# 1-Schematic_8052Explorer_DIP.net
KiCad netlist of a schematic drawn in EasyEDA
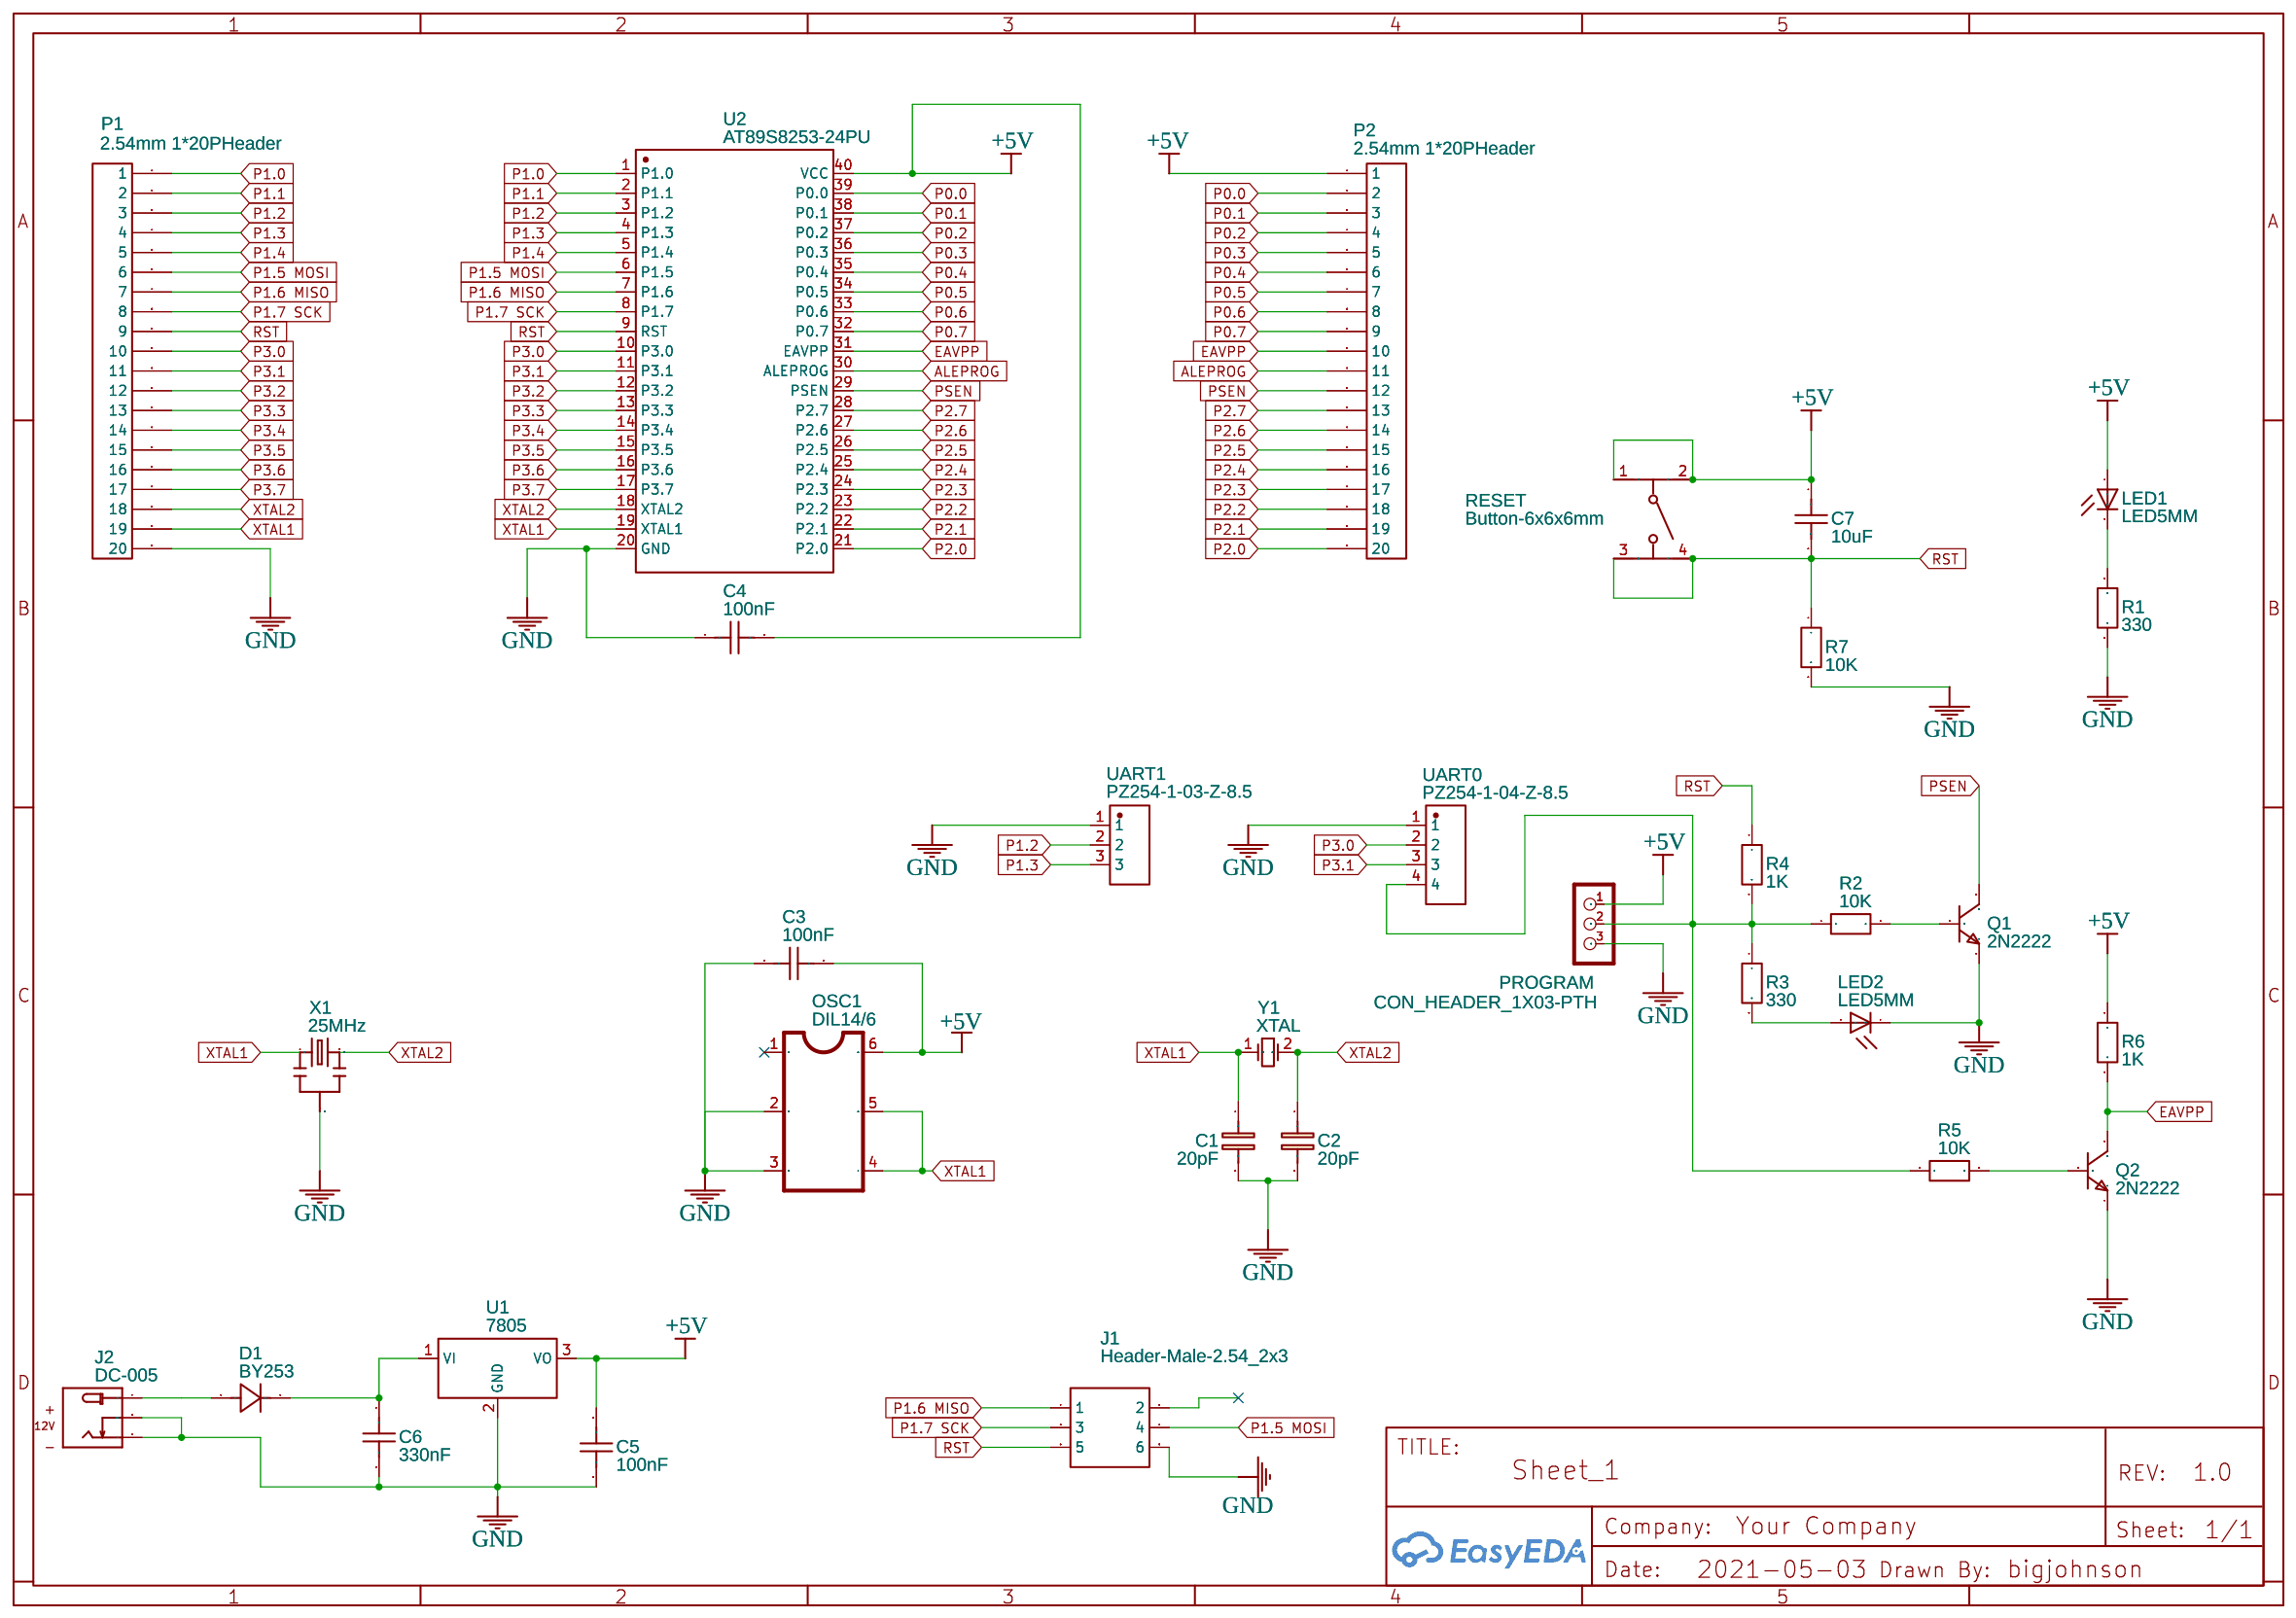
[diagram p0: schematic sheet]

(export (version "E")
  (design (tool "Eeschema 10.0.6"))
  (components
    (comp (ref "C1")
      (value "20pF")
      (fields (field (name "BOM_Supplier Part") "9000274010"))
      (libsource (lib "") (part "20pF copy"))
    )
    (comp (ref "C2")
      (value "20pF")
      (fields (field (name "BOM_Supplier Part") "9000274010"))
      (libsource (lib "") (part "20pF copy"))
    )
    (comp (ref "C3")
      (value "100nF")
      (fields
        (field (name "BOM_Manufacturer Part") "CT4-0805B103 K500")
        (field (name "BOM_Supplier Part") "C8033")
      )
      (libsource (lib "") (part "CT4-0805B103 K500"))
    )
    (comp (ref "C4")
      (value "100nF")
      (fields
        (field (name "BOM_Manufacturer Part") "CT4-0805B103 K500")
        (field (name "BOM_Supplier Part") "C8033")
      )
      (libsource (lib "") (part "CT4-0805B103 K500"))
    )
    (comp (ref "C5")
      (value "100nF")
      (fields
        (field (name "BOM_Manufacturer Part") "CT4-0805B103 K500")
        (field (name "BOM_Supplier Part") "C8033")
      )
      (libsource (lib "") (part "CT4-0805B103 K500_1"))
    )
    (comp (ref "C6")
      (value "330nF")
      (fields
        (field (name "BOM_Manufacturer Part") "CT4-0805B103 K500")
        (field (name "BOM_Supplier Part") "C8033")
      )
      (libsource (lib "") (part "CT4-0805B103 K500_1"))
    )
    (comp (ref "C7")
      (value "10uF")
      (fields
        (field (name "BOM_Manufacturer Part") "CT4-0805B103 K500")
        (field (name "BOM_Supplier Part") "C8033")
      )
      (libsource (lib "") (part "CT4-0805B103 K500_1"))
    )
    (comp (ref "D1")
      (value "BY253")
      (fields (field (name "BOM_Manufacturer Part") "MUR460") (field (name "BOM_Supplier Part") "C2990844"))
      (libsource (lib "") (part "MUR460_C2990844"))
    )
    (comp (ref "J1")
      (value "Header-Male-2.54_2x3")
      (fields (field (name "BOM_Supplier Part") "C65114"))
      (libsource (lib "") (part "Header-Male-2.54_2x3"))
    )
    (comp (ref "J2") (value "DC-005") (libsource (lib "") (part "DC-005")))
    (comp (ref "LED1") (value "LED5MM") (libsource (lib "") (part "LED5MM")))
    (comp (ref "LED2") (value "LED5MM") (libsource (lib "") (part "LED5MM_1")))
    (comp (ref "OSC1") (value "DIL14/6") (libsource (lib "") (part "DIL14/3")))
    (comp (ref "P1")
      (value "2.54mm 1*20PHeader")
      (fields (field (name "BOM_Supplier Part") "C50981"))
      (libsource (lib "") (part "2.54mm 1*20PHeader"))
    )
    (comp (ref "P2")
      (value "2.54mm 1*20PHeader")
      (fields (field (name "BOM_Supplier Part") "C50981"))
      (libsource (lib "") (part "2.54mm 1*20PHeader_1"))
    )
    (comp (ref "PROGRAM") (value "CON_HEADER_1X03-PTH") (libsource (lib "") (part "CON_HEADER_1X03-PTH")))
    (comp (ref "Q1")
      (value "2N2222")
      (fields (field (name "BOM_Supplier Part") "C118536"))
      (libsource (lib "") (part "2N2222"))
    )
    (comp (ref "Q2")
      (value "2N2222")
      (fields (field (name "BOM_Supplier Part") "C118536"))
      (libsource (lib "") (part "2N2222"))
    )
    (comp (ref "R1") (value "330") (libsource (lib "") (part "Res_AXIAL-0.4(1/4W)_EU")))
    (comp (ref "R2") (value "10K") (libsource (lib "") (part "Res_AXIAL-0.4(1/4W)_EU_1")))
    (comp (ref "R3") (value "330") (libsource (lib "") (part "Res_AXIAL-0.4(1/4W)_EU")))
    (comp (ref "R4") (value "1K") (libsource (lib "") (part "Res_AXIAL-0.4(1/4W)_EU")))
    (comp (ref "R5") (value "10K") (libsource (lib "") (part "Res_AXIAL-0.4(1/4W)_EU_1")))
    (comp (ref "R6") (value "1K") (libsource (lib "") (part "Res_AXIAL-0.4(1/4W)_EU")))
    (comp (ref "R7") (value "10K") (libsource (lib "") (part "Res_AXIAL-0.4(1/4W)_EU")))
    (comp (ref "RESET")
      (value "Button-6x6x6mm")
      (fields
        (field (name "BOM_Manufacturer Part") "Switch,6*6*6Plastic head,260G, 0.25mm,Straight line")
        (field (name "BOM_Supplier Part") "C71836")
      )
      (libsource (lib "") (part "Button-6x6x6mm"))
    )
    (comp (ref "U1")
      (value "7805")
      (fields (field (name "BOM_Supplier Part") "C305416"))
      (libsource (lib "") (part "7805"))
    )
    (comp (ref "U2") (value "AT89S8253-24PU") (libsource (lib "") (part "AT89S8253-24PU")))
    (comp (ref "UART0")
      (value "PZ254-1-04-Z-8.5")
      (fields (field (name "BOM_Supplier Part") "C2894927"))
      (libsource (lib "") (part "PZ254-1-04-Z-8.5"))
    )
    (comp (ref "UART1")
      (value "PZ254-1-03-Z-8.5")
      (fields (field (name "BOM_Supplier Part") "C2894926"))
      (libsource (lib "") (part "PZ254-1-03-Z-8.5"))
    )
    (comp (ref "X1")
      (value "25MHz")
      (fields
        (field (name "BOM_Manufacturer Part") "Resonator 433.92MHZ")
        (field (name "BOM_Supplier Part") "C71016")
      )
      (libsource (lib "") (part "Ceramic Resonator 16 MHz"))
    )
    (comp (ref "Y1") (value "XTAL") (libsource (lib "") (part "XTAL")))
  )
  (nets
    (net (code "1") (name "+5V") (class "Default")
      (node (ref "C3") (pin "2") (pinfunction "2_2") (pintype "unspecified"))
      (node (ref "C4") (pin "2") (pinfunction "2_2") (pintype "unspecified"))
      (node (ref "C5") (pin "1") (pinfunction "1_1") (pintype "unspecified"))
      (node (ref "C7") (pin "1") (pinfunction "1_1") (pintype "unspecified"))
      (node (ref "LED1") (pin "A") (pinfunction "A_A") (pintype "unspecified"))
      (node (ref "OSC1") (pin "6") (pinfunction "6_6") (pintype "unspecified"))
      (node (ref "P2") (pin "1") (pinfunction "1_1") (pintype "input"))
      (node (ref "PROGRAM") (pin "1") (pinfunction "1_1") (pintype "unspecified"))
      (node (ref "R6") (pin "1") (pinfunction "1_1") (pintype "unspecified"))
      (node (ref "RESET") (pin "1") (pinfunction "1_1") (pintype "unspecified"))
      (node (ref "RESET") (pin "2") (pinfunction "2_2") (pintype "unspecified"))
      (node (ref "U1") (pin "3") (pinfunction "VO_3") (pintype "unspecified"))
      (node (ref "U2") (pin "40") (pinfunction "VCC_40") (pintype "unspecified"))
    )
    (net (code "2") (name "ALEPROG") (class "Default")
      (node (ref "P2") (pin "11") (pinfunction "11_11") (pintype "input"))
      (node (ref "U2") (pin "30") (pinfunction "ALEPROG_30") (pintype "unspecified"))
    )
    (net (code "3") (name "EAVPP") (class "Default")
      (node (ref "P2") (pin "10") (pinfunction "10_10") (pintype "input"))
      (node (ref "Q2") (pin "3") (pinfunction "C_3") (pintype "unspecified"))
      (node (ref "R6") (pin "2") (pinfunction "2_2") (pintype "unspecified"))
      (node (ref "U2") (pin "31") (pinfunction "EAVPP_31") (pintype "unspecified"))
    )
    (net (code "4") (name "GND") (class "Default")
      (node (ref "C1") (pin "2") (pinfunction "1_2") (pintype "unspecified"))
      (node (ref "C2") (pin "2") (pinfunction "1_2") (pintype "unspecified"))
      (node (ref "C3") (pin "1") (pinfunction "1_1") (pintype "unspecified"))
      (node (ref "C4") (pin "1") (pinfunction "1_1") (pintype "unspecified"))
      (node (ref "C5") (pin "2") (pinfunction "2_2") (pintype "unspecified"))
      (node (ref "C6") (pin "2") (pinfunction "2_2") (pintype "unspecified"))
      (node (ref "J1") (pin "6") (pinfunction "6_6") (pintype "input"))
      (node (ref "J2") (pin "-1") (pinfunction "-_-1") (pintype "unspecified"))
      (node (ref "J2") (pin "-2") (pinfunction "CDN_-2") (pintype "unspecified"))
      (node (ref "LED2") (pin "K") (pinfunction "C_K") (pintype "unspecified"))
      (node (ref "OSC1") (pin "2") (pinfunction "2_2") (pintype "unspecified"))
      (node (ref "OSC1") (pin "3") (pinfunction "3_3") (pintype "unspecified"))
      (node (ref "P1") (pin "20") (pinfunction "20_20") (pintype "input"))
      (node (ref "PROGRAM") (pin "3") (pinfunction "3_3") (pintype "unspecified"))
      (node (ref "Q1") (pin "1") (pinfunction "E_1") (pintype "unspecified"))
      (node (ref "Q2") (pin "1") (pinfunction "E_1") (pintype "unspecified"))
      (node (ref "R1") (pin "2") (pinfunction "2_2") (pintype "unspecified"))
      (node (ref "R7") (pin "2") (pinfunction "2_2") (pintype "unspecified"))
      (node (ref "U1") (pin "2") (pinfunction "GND_2") (pintype "unspecified"))
      (node (ref "U2") (pin "20") (pinfunction "GND_20") (pintype "unspecified"))
      (node (ref "UART0") (pin "1") (pinfunction "1_1") (pintype "unspecified"))
      (node (ref "UART1") (pin "1") (pinfunction "1_1") (pintype "unspecified"))
      (node (ref "X1") (pin "2") (pinfunction "2_2") (pintype "unspecified"))
    )
    (net (code "5") (name "Net-(D1-A)") (class "Default")
      (node (ref "D1") (pin "2") (pinfunction "A_2") (pintype "unspecified"))
      (node (ref "J2") (pin "+") (pinfunction "+_+") (pintype "unspecified"))
    )
    (net (code "6") (name "Net-(D1-K)") (class "Default")
      (node (ref "C6") (pin "1") (pinfunction "1_1") (pintype "unspecified"))
      (node (ref "D1") (pin "1") (pinfunction "K_1") (pintype "unspecified"))
      (node (ref "U1") (pin "1") (pinfunction "VI_1") (pintype "unspecified"))
    )
    (net (code "7") (name "Net-(LED1-C)") (class "Default")
      (node (ref "LED1") (pin "K") (pinfunction "C_K") (pintype "unspecified"))
      (node (ref "R1") (pin "1") (pinfunction "1_1") (pintype "unspecified"))
    )
    (net (code "8") (name "Net-(LED2-PadA)") (class "Default")
      (node (ref "LED2") (pin "A") (pinfunction "A_A") (pintype "unspecified"))
      (node (ref "R3") (pin "2") (pinfunction "2_2") (pintype "unspecified"))
    )
    (net (code "9") (name "Net-(PROGRAM-Pad2)") (class "Default")
      (node (ref "PROGRAM") (pin "2") (pinfunction "2_2") (pintype "unspecified"))
      (node (ref "R2") (pin "1") (pinfunction "1_1") (pintype "unspecified"))
      (node (ref "R3") (pin "1") (pinfunction "1_1") (pintype "unspecified"))
      (node (ref "R4") (pin "2") (pinfunction "2_2") (pintype "unspecified"))
      (node (ref "R5") (pin "1") (pinfunction "1_1") (pintype "unspecified"))
      (node (ref "UART0") (pin "4") (pinfunction "4_4") (pintype "unspecified"))
    )
    (net (code "10") (name "Net-(Q1-B)") (class "Default")
      (node (ref "Q1") (pin "2") (pinfunction "B_2") (pintype "unspecified"))
      (node (ref "R2") (pin "2") (pinfunction "2_2") (pintype "unspecified"))
    )
    (net (code "11") (name "Net-(Q2-B)") (class "Default")
      (node (ref "Q2") (pin "2") (pinfunction "B_2") (pintype "unspecified"))
      (node (ref "R5") (pin "2") (pinfunction "2_2") (pintype "unspecified"))
    )
    (net (code "12") (name "P0.0") (class "Default")
      (node (ref "P2") (pin "2") (pinfunction "2_2") (pintype "input"))
      (node (ref "U2") (pin "39") (pinfunction "P0.0_39") (pintype "unspecified"))
    )
    (net (code "13") (name "P0.1") (class "Default")
      (node (ref "P2") (pin "3") (pinfunction "3_3") (pintype "input"))
      (node (ref "U2") (pin "38") (pinfunction "P0.1_38") (pintype "unspecified"))
    )
    (net (code "14") (name "P0.2") (class "Default")
      (node (ref "P2") (pin "4") (pinfunction "4_4") (pintype "input"))
      (node (ref "U2") (pin "37") (pinfunction "P0.2_37") (pintype "unspecified"))
    )
    (net (code "15") (name "P0.3") (class "Default")
      (node (ref "P2") (pin "5") (pinfunction "5_5") (pintype "input"))
      (node (ref "U2") (pin "36") (pinfunction "P0.3_36") (pintype "unspecified"))
    )
    (net (code "16") (name "P0.4") (class "Default")
      (node (ref "P2") (pin "6") (pinfunction "6_6") (pintype "input"))
      (node (ref "U2") (pin "35") (pinfunction "P0.4_35") (pintype "unspecified"))
    )
    (net (code "17") (name "P0.5") (class "Default")
      (node (ref "P2") (pin "7") (pinfunction "7_7") (pintype "input"))
      (node (ref "U2") (pin "34") (pinfunction "P0.5_34") (pintype "unspecified"))
    )
    (net (code "18") (name "P0.6") (class "Default")
      (node (ref "P2") (pin "8") (pinfunction "8_8") (pintype "input"))
      (node (ref "U2") (pin "33") (pinfunction "P0.6_33") (pintype "unspecified"))
    )
    (net (code "19") (name "P0.7") (class "Default")
      (node (ref "P2") (pin "9") (pinfunction "9_9") (pintype "input"))
      (node (ref "U2") (pin "32") (pinfunction "P0.7_32") (pintype "unspecified"))
    )
    (net (code "20") (name "P1.0") (class "Default")
      (node (ref "P1") (pin "1") (pinfunction "1_1") (pintype "input"))
      (node (ref "U2") (pin "1") (pinfunction "P1.0_1") (pintype "unspecified"))
    )
    (net (code "21") (name "P1.1") (class "Default")
      (node (ref "P1") (pin "2") (pinfunction "2_2") (pintype "input"))
      (node (ref "U2") (pin "2") (pinfunction "P1.1_2") (pintype "unspecified"))
    )
    (net (code "22") (name "P1.2") (class "Default")
      (node (ref "P1") (pin "3") (pinfunction "3_3") (pintype "input"))
      (node (ref "U2") (pin "3") (pinfunction "P1.2_3") (pintype "unspecified"))
      (node (ref "UART1") (pin "2") (pinfunction "2_2") (pintype "unspecified"))
    )
    (net (code "23") (name "P1.3") (class "Default")
      (node (ref "P1") (pin "4") (pinfunction "4_4") (pintype "input"))
      (node (ref "U2") (pin "4") (pinfunction "P1.3_4") (pintype "unspecified"))
      (node (ref "UART1") (pin "3") (pinfunction "3_3") (pintype "unspecified"))
    )
    (net (code "24") (name "P1.4") (class "Default")
      (node (ref "P1") (pin "5") (pinfunction "5_5") (pintype "input"))
      (node (ref "U2") (pin "5") (pinfunction "P1.4_5") (pintype "unspecified"))
    )
    (net (code "25") (name "P1.5 MOSI") (class "Default")
      (node (ref "J1") (pin "4") (pinfunction "4_4") (pintype "input"))
      (node (ref "P1") (pin "6") (pinfunction "6_6") (pintype "input"))
      (node (ref "U2") (pin "6") (pinfunction "P1.5_6") (pintype "unspecified"))
    )
    (net (code "26") (name "P1.6 MISO") (class "Default")
      (node (ref "J1") (pin "1") (pinfunction "1_1") (pintype "input"))
      (node (ref "P1") (pin "7") (pinfunction "7_7") (pintype "input"))
      (node (ref "U2") (pin "7") (pinfunction "P1.6_7") (pintype "unspecified"))
    )
    (net (code "27") (name "P1.7 SCK") (class "Default")
      (node (ref "J1") (pin "3") (pinfunction "3_3") (pintype "input"))
      (node (ref "P1") (pin "8") (pinfunction "8_8") (pintype "input"))
      (node (ref "U2") (pin "8") (pinfunction "P1.7_8") (pintype "unspecified"))
    )
    (net (code "28") (name "P2.0") (class "Default")
      (node (ref "P2") (pin "20") (pinfunction "20_20") (pintype "input"))
      (node (ref "U2") (pin "21") (pinfunction "P2.0_21") (pintype "unspecified"))
    )
    (net (code "29") (name "P2.1") (class "Default")
      (node (ref "P2") (pin "19") (pinfunction "19_19") (pintype "input"))
      (node (ref "U2") (pin "22") (pinfunction "P2.1_22") (pintype "unspecified"))
    )
    (net (code "30") (name "P2.2") (class "Default")
      (node (ref "P2") (pin "18") (pinfunction "18_18") (pintype "input"))
      (node (ref "U2") (pin "23") (pinfunction "P2.2_23") (pintype "unspecified"))
    )
    (net (code "31") (name "P2.3") (class "Default")
      (node (ref "P2") (pin "17") (pinfunction "17_17") (pintype "input"))
      (node (ref "U2") (pin "24") (pinfunction "P2.3_24") (pintype "unspecified"))
    )
    (net (code "32") (name "P2.4") (class "Default")
      (node (ref "P2") (pin "16") (pinfunction "16_16") (pintype "input"))
      (node (ref "U2") (pin "25") (pinfunction "P2.4_25") (pintype "unspecified"))
    )
    (net (code "33") (name "P2.5") (class "Default")
      (node (ref "P2") (pin "15") (pinfunction "15_15") (pintype "input"))
      (node (ref "U2") (pin "26") (pinfunction "P2.5_26") (pintype "unspecified"))
    )
    (net (code "34") (name "P2.6") (class "Default")
      (node (ref "P2") (pin "14") (pinfunction "14_14") (pintype "input"))
      (node (ref "U2") (pin "27") (pinfunction "P2.6_27") (pintype "unspecified"))
    )
    (net (code "35") (name "P2.7") (class "Default")
      (node (ref "P2") (pin "13") (pinfunction "13_13") (pintype "input"))
      (node (ref "U2") (pin "28") (pinfunction "P2.7_28") (pintype "unspecified"))
    )
    (net (code "36") (name "P3.0") (class "Default")
      (node (ref "P1") (pin "10") (pinfunction "10_10") (pintype "input"))
      (node (ref "U2") (pin "10") (pinfunction "P3.0_10") (pintype "unspecified"))
      (node (ref "UART0") (pin "2") (pinfunction "2_2") (pintype "unspecified"))
    )
    (net (code "37") (name "P3.1") (class "Default")
      (node (ref "P1") (pin "11") (pinfunction "11_11") (pintype "input"))
      (node (ref "U2") (pin "11") (pinfunction "P3.1_11") (pintype "unspecified"))
      (node (ref "UART0") (pin "3") (pinfunction "3_3") (pintype "unspecified"))
    )
    (net (code "38") (name "P3.2") (class "Default")
      (node (ref "P1") (pin "12") (pinfunction "12_12") (pintype "input"))
      (node (ref "U2") (pin "12") (pinfunction "P3.2_12") (pintype "unspecified"))
    )
    (net (code "39") (name "P3.3") (class "Default")
      (node (ref "P1") (pin "13") (pinfunction "13_13") (pintype "input"))
      (node (ref "U2") (pin "13") (pinfunction "P3.3_13") (pintype "unspecified"))
    )
    (net (code "40") (name "P3.4") (class "Default")
      (node (ref "P1") (pin "14") (pinfunction "14_14") (pintype "input"))
      (node (ref "U2") (pin "14") (pinfunction "P3.4_14") (pintype "unspecified"))
    )
    (net (code "41") (name "P3.5") (class "Default")
      (node (ref "P1") (pin "15") (pinfunction "15_15") (pintype "input"))
      (node (ref "U2") (pin "15") (pinfunction "P3.5_15") (pintype "unspecified"))
    )
    (net (code "42") (name "P3.6") (class "Default")
      (node (ref "P1") (pin "16") (pinfunction "16_16") (pintype "input"))
      (node (ref "U2") (pin "16") (pinfunction "P3.6_16") (pintype "unspecified"))
    )
    (net (code "43") (name "P3.7") (class "Default")
      (node (ref "P1") (pin "17") (pinfunction "17_17") (pintype "input"))
      (node (ref "U2") (pin "17") (pinfunction "P3.7_17") (pintype "unspecified"))
    )
    (net (code "44") (name "PSEN") (class "Default")
      (node (ref "P2") (pin "12") (pinfunction "12_12") (pintype "input"))
      (node (ref "Q1") (pin "3") (pinfunction "C_3") (pintype "unspecified"))
      (node (ref "U2") (pin "29") (pinfunction "PSEN_29") (pintype "unspecified"))
    )
    (net (code "45") (name "RST") (class "Default")
      (node (ref "C7") (pin "2") (pinfunction "2_2") (pintype "unspecified"))
      (node (ref "J1") (pin "5") (pinfunction "5_5") (pintype "input"))
      (node (ref "P1") (pin "9") (pinfunction "9_9") (pintype "input"))
      (node (ref "R4") (pin "1") (pinfunction "1_1") (pintype "unspecified"))
      (node (ref "R7") (pin "1") (pinfunction "1_1") (pintype "unspecified"))
      (node (ref "RESET") (pin "3") (pinfunction "3_3") (pintype "unspecified"))
      (node (ref "RESET") (pin "4") (pinfunction "4_4") (pintype "unspecified"))
      (node (ref "U2") (pin "9") (pinfunction "RST_9") (pintype "unspecified"))
    )
    (net (code "46") (name "XTAL1") (class "Default")
      (node (ref "C1") (pin "1") (pinfunction "1_1") (pintype "unspecified"))
      (node (ref "OSC1") (pin "4") (pinfunction "4_4") (pintype "unspecified"))
      (node (ref "OSC1") (pin "5") (pinfunction "5_5") (pintype "unspecified"))
      (node (ref "P1") (pin "19") (pinfunction "19_19") (pintype "input"))
      (node (ref "U2") (pin "19") (pinfunction "XTAL1_19") (pintype "unspecified"))
      (node (ref "X1") (pin "1") (pinfunction "1_1") (pintype "unspecified"))
      (node (ref "Y1") (pin "1") (pinfunction "OSC1_1") (pintype "unspecified"))
    )
    (net (code "47") (name "XTAL2") (class "Default")
      (node (ref "C2") (pin "1") (pinfunction "1_1") (pintype "unspecified"))
      (node (ref "P1") (pin "18") (pinfunction "18_18") (pintype "input"))
      (node (ref "U2") (pin "18") (pinfunction "XTAL2_18") (pintype "unspecified"))
      (node (ref "X1") (pin "3") (pinfunction "3_3") (pintype "unspecified"))
      (node (ref "Y1") (pin "2") (pinfunction "OSC2_2") (pintype "unspecified"))
    )
    (net (code "48") (name "unconnected-(J1-Pad2)") (class "Default")
      (node (ref "J1") (pin "2") (pinfunction "2_2") (pintype "input+no_connect"))
    )
    (net (code "49") (name "unconnected-(OSC1-Pad1)") (class "Default")
      (node (ref "OSC1") (pin "1") (pinfunction "1_1") (pintype "unspecified+no_connect"))
    )
  )
)
